# Schematic_v2.net
KiCad netlist of a schematic drawn in EAGLE
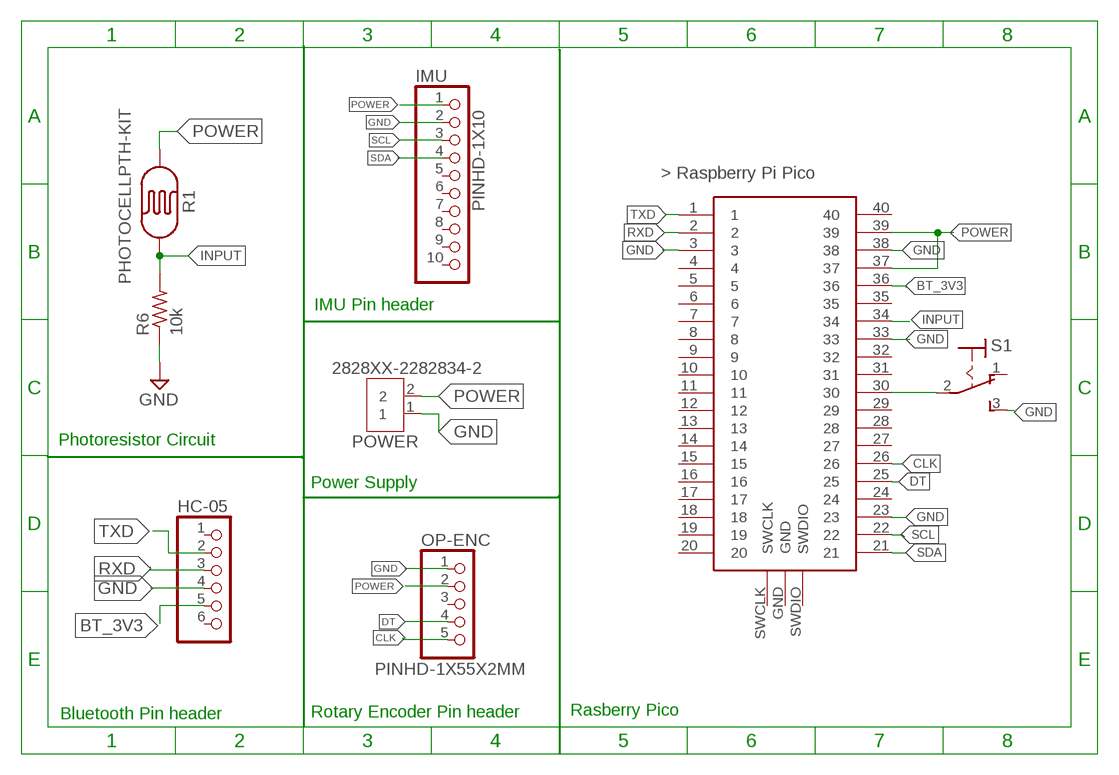
[diagram p0: schematic, sheet 1]

(export (version "E")
  (design (tool "Eeschema 10.0.6"))
  (components
    (comp (ref "HC-05")
      (value "PINHD-1X6")
      (footprint "eagle-import:1X06")
      (libsource (lib "eagle-import") (part "PINHD-1X6"))
    )
    (comp (ref "IMU")
      (value "PINHD-1X10")
      (footprint "eagle-import:1X10-BIG")
      (libsource (lib "eagle-import") (part "PINHD-1X10"))
    )
    (comp (ref "OP-ENC")
      (value "PINHD-1X55X2MM")
      (footprint "eagle-import:1_05X2MM")
      (libsource (lib "eagle-import") (part "PINHD-1X55X2MM"))
    )
    (comp (ref "PICO")
      (value "RASPBERRY-PI-PICO_TH")
      (footprint "eagle-import:FT_RASPBERRY-PI-PICO_TH")
      (libsource (lib "eagle-import") (part "RASPBERRY-PI-PICO_TH"))
    )
    (comp (ref "POWER")
      (value "2828XX-2282834-2")
      (footprint "eagle-import:TERMBLK_254-2N")
      (libsource (lib "eagle-import") (part "2828XX-2282834-2"))
    )
    (comp (ref "R1")
      (value "PHOTOCELLPTH-KIT")
      (footprint "eagle-import:PHOTOCELL-KIT")
      (libsource (lib "eagle-import") (part "PHOTOCELLPTH-KIT"))
    )
    (comp (ref "R6")
      (value "10k")
      (footprint "eagle-import:0207_10")
      (libsource (lib "eagle-import") (part "RESISTOR_1/4W_0207/10"))
    )
    (comp (ref "S1")
      (value "320-916")
      (footprint "eagle-import:320-916")
      (libsource (lib "eagle-import") (part "320-916"))
    )
  )
  (nets
    (net (code "1") (name "BT_3V3") (class "Default")
      (node (ref "HC-05") (pin "5") (pinfunction "5_5") (pintype "passive"))
      (node (ref "PICO") (pin "36") (pinfunction "36_36") (pintype "bidirectional"))
    )
    (net (code "2") (name "CLK") (class "Default")
      (node (ref "OP-ENC") (pin "5") (pinfunction "5_5") (pintype "passive"))
      (node (ref "PICO") (pin "26") (pinfunction "26_26") (pintype "bidirectional"))
    )
    (net (code "3") (name "DT") (class "Default")
      (node (ref "OP-ENC") (pin "4") (pinfunction "4_4") (pintype "passive"))
      (node (ref "PICO") (pin "25") (pinfunction "25_25") (pintype "bidirectional"))
    )
    (net (code "4") (name "GND") (class "Default")
      (node (ref "HC-05") (pin "4") (pinfunction "4_4") (pintype "passive"))
      (node (ref "IMU") (pin "2") (pinfunction "2_2") (pintype "passive"))
      (node (ref "OP-ENC") (pin "1") (pinfunction "1_1") (pintype "passive"))
      (node (ref "PICO") (pin "23") (pinfunction "23_23") (pintype "bidirectional"))
      (node (ref "PICO") (pin "3") (pinfunction "3_3") (pintype "bidirectional"))
      (node (ref "PICO") (pin "33") (pinfunction "33_33") (pintype "bidirectional"))
      (node (ref "PICO") (pin "38") (pinfunction "38_38") (pintype "bidirectional"))
      (node (ref "POWER") (pin "1") (pinfunction "1_1") (pintype "bidirectional"))
      (node (ref "R6") (pin "1") (pinfunction "1_1") (pintype "passive"))
      (node (ref "S1") (pin "3") (pinfunction "S_3") (pintype "passive"))
    )
    (net (code "5") (name "INPUT") (class "Default")
      (node (ref "PICO") (pin "34") (pinfunction "34_34") (pintype "bidirectional"))
      (node (ref "R1") (pin "1") (pinfunction "P$1_1") (pintype "bidirectional"))
      (node (ref "R6") (pin "2") (pinfunction "2_2") (pintype "passive"))
    )
    (net (code "6") (name "Net-(S1-P)") (class "Default")
      (node (ref "PICO") (pin "30") (pinfunction "30_30") (pintype "bidirectional"))
      (node (ref "S1") (pin "2") (pinfunction "P_2") (pintype "passive"))
    )
    (net (code "7") (name "POWER") (class "Default")
      (node (ref "IMU") (pin "1") (pinfunction "1_1") (pintype "passive"))
      (node (ref "OP-ENC") (pin "2") (pinfunction "2_2") (pintype "passive"))
      (node (ref "PICO") (pin "37") (pinfunction "37_37") (pintype "bidirectional"))
      (node (ref "PICO") (pin "39") (pinfunction "39_39") (pintype "bidirectional"))
      (node (ref "POWER") (pin "2") (pinfunction "2_2") (pintype "bidirectional"))
      (node (ref "R1") (pin "2") (pinfunction "P$2_2") (pintype "bidirectional"))
    )
    (net (code "8") (name "RXD") (class "Default")
      (node (ref "HC-05") (pin "3") (pinfunction "3_3") (pintype "passive"))
      (node (ref "PICO") (pin "2") (pinfunction "2_2") (pintype "bidirectional"))
    )
    (net (code "9") (name "SCL") (class "Default")
      (node (ref "IMU") (pin "3") (pinfunction "3_3") (pintype "passive"))
      (node (ref "PICO") (pin "22") (pinfunction "22_22") (pintype "bidirectional"))
    )
    (net (code "10") (name "SDA") (class "Default")
      (node (ref "IMU") (pin "4") (pinfunction "4_4") (pintype "passive"))
      (node (ref "PICO") (pin "21") (pinfunction "21_21") (pintype "bidirectional"))
    )
    (net (code "11") (name "TXD") (class "Default")
      (node (ref "HC-05") (pin "2") (pinfunction "2_2") (pintype "passive"))
      (node (ref "PICO") (pin "1") (pinfunction "1_1") (pintype "bidirectional"))
    )
    (net (code "12") (name "unconnected-(HC-05-Pad1)") (class "Default")
      (node (ref "HC-05") (pin "1") (pinfunction "1_1") (pintype "passive"))
    )
    (net (code "13") (name "unconnected-(HC-05-Pad6)") (class "Default")
      (node (ref "HC-05") (pin "6") (pinfunction "6_6") (pintype "passive"))
    )
    (net (code "14") (name "unconnected-(IMU-Pad5)") (class "Default")
      (node (ref "IMU") (pin "5") (pinfunction "5_5") (pintype "passive"))
    )
    (net (code "15") (name "unconnected-(IMU-Pad6)") (class "Default")
      (node (ref "IMU") (pin "6") (pinfunction "6_6") (pintype "passive"))
    )
    (net (code "16") (name "unconnected-(IMU-Pad7)") (class "Default")
      (node (ref "IMU") (pin "7") (pinfunction "7_7") (pintype "passive"))
    )
    (net (code "17") (name "unconnected-(IMU-Pad8)") (class "Default")
      (node (ref "IMU") (pin "8") (pinfunction "8_8") (pintype "passive"))
    )
    (net (code "18") (name "unconnected-(IMU-Pad9)") (class "Default")
      (node (ref "IMU") (pin "9") (pinfunction "9_9") (pintype "passive"))
    )
    (net (code "19") (name "unconnected-(IMU-Pad10)") (class "Default")
      (node (ref "IMU") (pin "10") (pinfunction "10_10") (pintype "passive"))
    )
    (net (code "20") (name "unconnected-(OP-ENC-Pad3)") (class "Default")
      (node (ref "OP-ENC") (pin "3") (pinfunction "3_3") (pintype "passive"))
    )
    (net (code "21") (name "unconnected-(PICO-Pad4)") (class "Default")
      (node (ref "PICO") (pin "4") (pinfunction "4_4") (pintype "bidirectional"))
    )
    (net (code "22") (name "unconnected-(PICO-Pad5)") (class "Default")
      (node (ref "PICO") (pin "5") (pinfunction "5_5") (pintype "bidirectional"))
    )
    (net (code "23") (name "unconnected-(PICO-Pad6)") (class "Default")
      (node (ref "PICO") (pin "6") (pinfunction "6_6") (pintype "bidirectional"))
    )
    (net (code "24") (name "unconnected-(PICO-Pad7)") (class "Default")
      (node (ref "PICO") (pin "7") (pinfunction "7_7") (pintype "bidirectional"))
    )
    (net (code "25") (name "unconnected-(PICO-Pad8)") (class "Default")
      (node (ref "PICO") (pin "8") (pinfunction "8_8") (pintype "bidirectional"))
    )
    (net (code "26") (name "unconnected-(PICO-Pad9)") (class "Default")
      (node (ref "PICO") (pin "9") (pinfunction "9_9") (pintype "bidirectional"))
    )
    (net (code "27") (name "unconnected-(PICO-Pad10)") (class "Default")
      (node (ref "PICO") (pin "10") (pinfunction "10_10") (pintype "bidirectional"))
    )
    (net (code "28") (name "unconnected-(PICO-Pad11)") (class "Default")
      (node (ref "PICO") (pin "11") (pinfunction "11_11") (pintype "bidirectional"))
    )
    (net (code "29") (name "unconnected-(PICO-Pad12)") (class "Default")
      (node (ref "PICO") (pin "12") (pinfunction "12_12") (pintype "bidirectional"))
    )
    (net (code "30") (name "unconnected-(PICO-Pad13)") (class "Default")
      (node (ref "PICO") (pin "13") (pinfunction "13_13") (pintype "bidirectional"))
    )
    (net (code "31") (name "unconnected-(PICO-Pad14)") (class "Default")
      (node (ref "PICO") (pin "14") (pinfunction "14_14") (pintype "bidirectional"))
    )
    (net (code "32") (name "unconnected-(PICO-Pad15)") (class "Default")
      (node (ref "PICO") (pin "15") (pinfunction "15_15") (pintype "bidirectional"))
    )
    (net (code "33") (name "unconnected-(PICO-Pad16)") (class "Default")
      (node (ref "PICO") (pin "16") (pinfunction "16_16") (pintype "bidirectional"))
    )
    (net (code "34") (name "unconnected-(PICO-Pad17)") (class "Default")
      (node (ref "PICO") (pin "17") (pinfunction "17_17") (pintype "bidirectional"))
    )
    (net (code "35") (name "unconnected-(PICO-Pad18)") (class "Default")
      (node (ref "PICO") (pin "18") (pinfunction "18_18") (pintype "bidirectional"))
    )
    (net (code "36") (name "unconnected-(PICO-Pad19)") (class "Default")
      (node (ref "PICO") (pin "19") (pinfunction "19_19") (pintype "bidirectional"))
    )
    (net (code "37") (name "unconnected-(PICO-Pad20)") (class "Default")
      (node (ref "PICO") (pin "20") (pinfunction "20_20") (pintype "bidirectional"))
    )
    (net (code "38") (name "unconnected-(PICO-Pad24)") (class "Default")
      (node (ref "PICO") (pin "24") (pinfunction "24_24") (pintype "bidirectional"))
    )
    (net (code "39") (name "unconnected-(PICO-Pad27)") (class "Default")
      (node (ref "PICO") (pin "27") (pinfunction "27_27") (pintype "bidirectional"))
    )
    (net (code "40") (name "unconnected-(PICO-Pad28)") (class "Default")
      (node (ref "PICO") (pin "28") (pinfunction "28_28") (pintype "bidirectional"))
    )
    (net (code "41") (name "unconnected-(PICO-Pad29)") (class "Default")
      (node (ref "PICO") (pin "29") (pinfunction "29_29") (pintype "bidirectional"))
    )
    (net (code "42") (name "unconnected-(PICO-Pad31)") (class "Default")
      (node (ref "PICO") (pin "31") (pinfunction "31_31") (pintype "bidirectional"))
    )
    (net (code "43") (name "unconnected-(PICO-Pad32)") (class "Default")
      (node (ref "PICO") (pin "32") (pinfunction "32_32") (pintype "bidirectional"))
    )
    (net (code "44") (name "unconnected-(PICO-Pad35)") (class "Default")
      (node (ref "PICO") (pin "35") (pinfunction "35_35") (pintype "bidirectional"))
    )
    (net (code "45") (name "unconnected-(PICO-Pad40)") (class "Default")
      (node (ref "PICO") (pin "40") (pinfunction "40_40") (pintype "bidirectional"))
    )
    (net (code "46") (name "unconnected-(PICO-PadGND)") (class "Default")
      (node (ref "PICO") (pin "GND") (pinfunction "GND_GND") (pintype "bidirectional"))
    )
    (net (code "47") (name "unconnected-(PICO-PadSWCLK)") (class "Default")
      (node (ref "PICO") (pin "SWCLK") (pinfunction "SWCLK_SWCLK") (pintype "bidirectional"))
    )
    (net (code "48") (name "unconnected-(PICO-PadSWDIO)") (class "Default")
      (node (ref "PICO") (pin "SWDIO") (pinfunction "SWDIO_SWDIO") (pintype "bidirectional"))
    )
    (net (code "49") (name "unconnected-(S1-O-Pad1)") (class "Default")
      (node (ref "S1") (pin "1") (pinfunction "O_1") (pintype "passive"))
    )
  )
)
